# Power_Distribution_-_BMS_Rear_Camera_and.net
KiCad netlist of a schematic drawn in Altium Designer
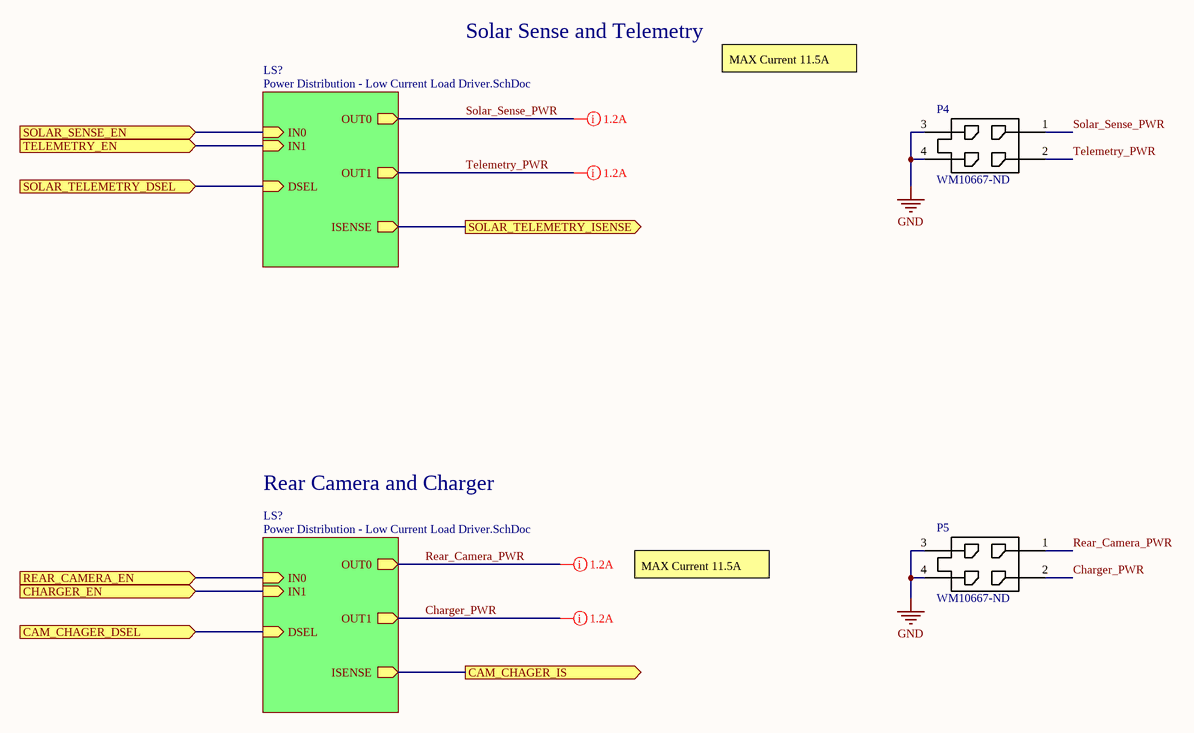
[diagram p0: Power Distribution - BMS,Rear Camera, and Charger.SchDoc]

(export (version "E")
  (design (tool "Eeschema 10.0.6"))
  (components
    (comp (ref "P4")
      (value "CONN 4POS MICRO-FIT 3mm")
      (footprint "CONN 4POS MICROFIT (2x2)")
      (fields
        (field (name "MANUFACTURER") "Molex, LLC")
        (field (name "MANUFACTURER PART NUMBER") "430450427")
        (field (name "SUPPLIER PART NUMBER 1") "WM10667-ND")
      )
      (libsource (lib "Schematic Diagrams") (part "CONN 4POS MICRO-FIT 3mm"))
    )
    (comp (ref "P5")
      (value "CONN 4POS MICRO-FIT 3mm")
      (footprint "CONN 4POS MICROFIT (2x2)")
      (fields
        (field (name "MANUFACTURER") "Molex, LLC")
        (field (name "MANUFACTURER PART NUMBER") "430450427")
        (field (name "SUPPLIER PART NUMBER 1") "WM10667-ND")
      )
      (libsource (lib "Schematic Diagrams") (part "CONN 4POS MICRO-FIT 3mm"))
    )
  )
  (nets
    (net (code "4") (name "/Charger_PWR") (class "Default")
      (node (ref "P5") (pin "2") (pinfunction "2_2") (pintype "passive"))
    )
    (net (code "6") (name "/Rear_Camera_PWR") (class "Default")
      (node (ref "P5") (pin "1") (pinfunction "1_1") (pintype "passive"))
    )
    (net (code "10") (name "/Solar_Sense_PWR") (class "Default")
      (node (ref "P4") (pin "1") (pinfunction "1_1") (pintype "passive"))
    )
    (net (code "12") (name "/Telemetry_PWR") (class "Default")
      (node (ref "P4") (pin "2") (pinfunction "2_2") (pintype "passive"))
    )
    (net (code "13") (name "GND") (class "Default")
      (node (ref "P4") (pin "3") (pinfunction "3_3") (pintype "passive"))
      (node (ref "P4") (pin "4") (pinfunction "4_4") (pintype "passive"))
      (node (ref "P5") (pin "3") (pinfunction "3_3") (pintype "passive"))
      (node (ref "P5") (pin "4") (pinfunction "4_4") (pintype "passive"))
    )
  )
)
